# SCH_DC.net
KiCad netlist of a schematic drawn in EasyEDA
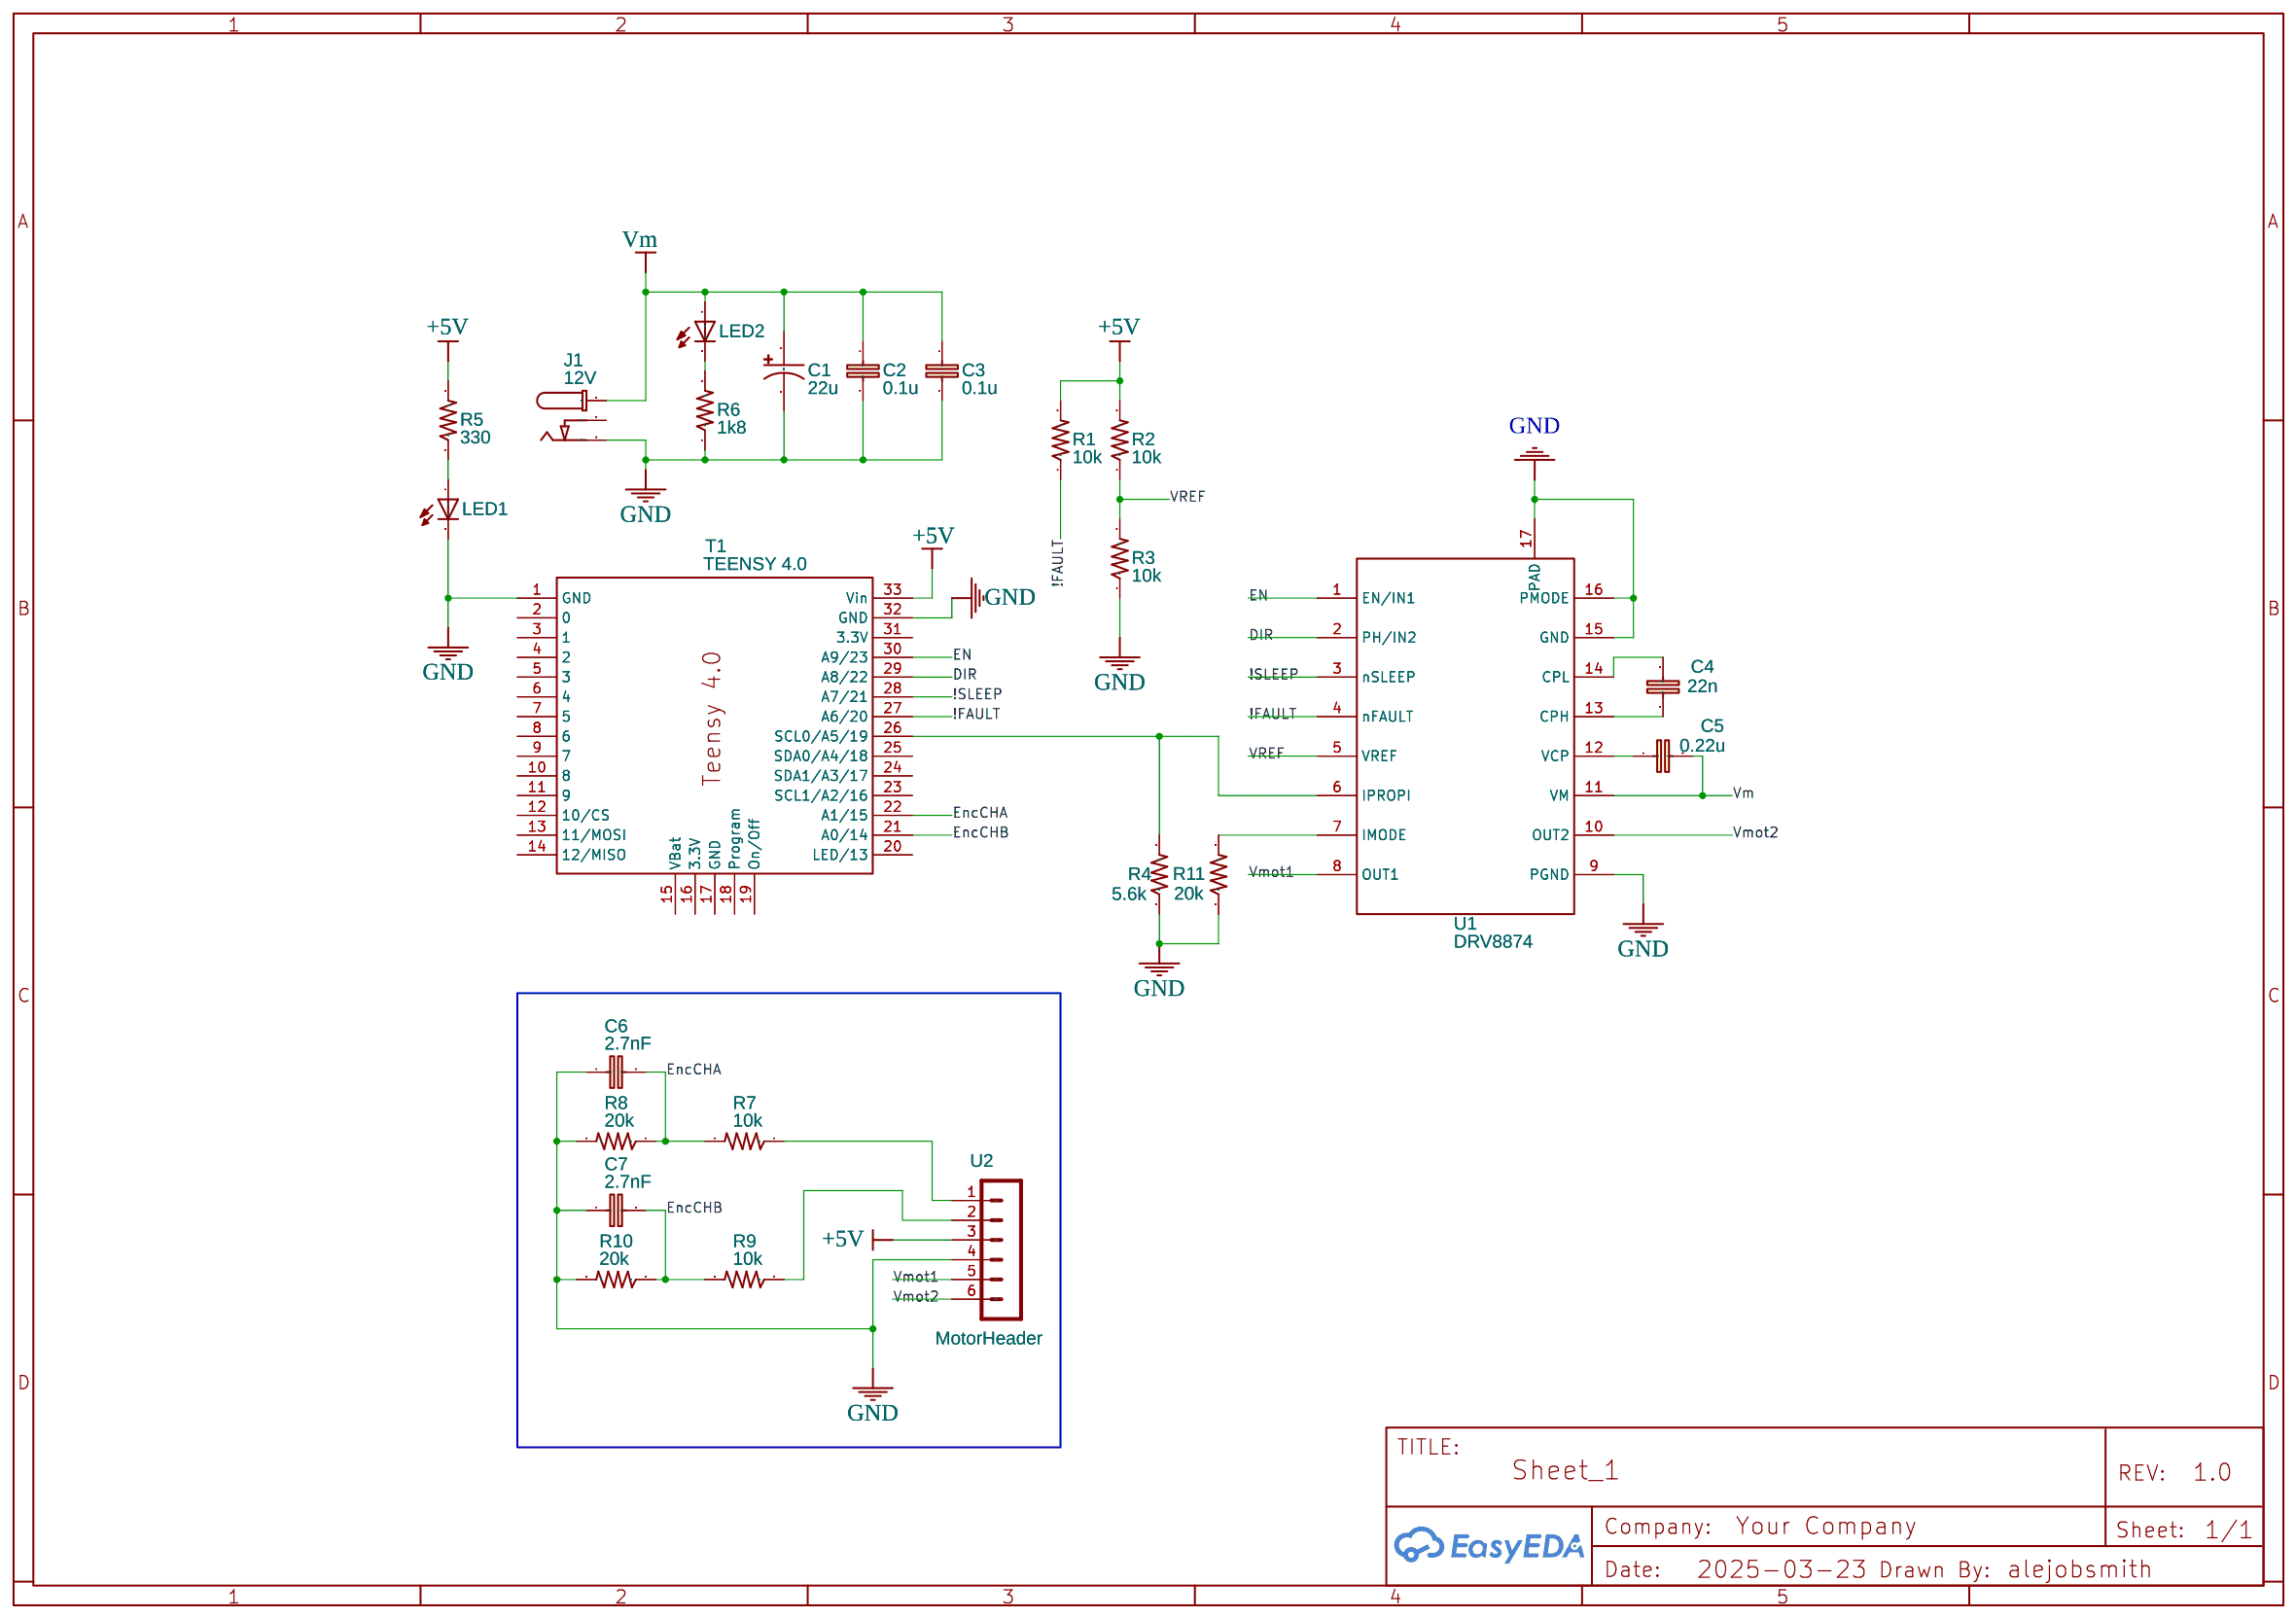
[diagram p0: schematic sheet]

(export (version "E")
  (design (tool "Eeschema 10.0.6"))
  (components
    (comp (ref "C1") (value "22u") (libsource (lib "") (part "Cap_Electrolytic(SMD)_D5.0XH5.5_US")))
    (comp (ref "C2") (value "0.1u") (libsource (lib "") (part "CAPACITOR_NPOL-1206_1")))
    (comp (ref "C3") (value "0.1u") (libsource (lib "") (part "CAPACITOR_NPOL-1206_1")))
    (comp (ref "C4") (value "22n") (libsource (lib "") (part "CAPACITOR_NPOL-1206_2")))
    (comp (ref "C5") (value "0.22u") (libsource (lib "") (part "CAPACITOR_NPOL-1206")))
    (comp (ref "C6") (value "2.7nF") (libsource (lib "") (part "CAPACITOR_NPOL-1206")))
    (comp (ref "C7") (value "2.7nF") (libsource (lib "") (part "CAPACITOR_NPOL-1206")))
    (comp (ref "J1") (value "12V") (libsource (lib "") (part "CON_DC_M-DC_PTH2")))
    (comp (ref "LED1") (value "LED_5MM") (libsource (lib "") (part "LED_5MM")))
    (comp (ref "LED2") (value "LED_5MM") (libsource (lib "") (part "LED_5MM")))
    (comp (ref "R1") (value "10k") (libsource (lib "") (part "R-US_R1206_1")))
    (comp (ref "R2") (value "10k") (libsource (lib "") (part "R-US_R1206_1")))
    (comp (ref "R3") (value "10k") (libsource (lib "") (part "R-US_R1206_1")))
    (comp (ref "R4") (value "5.6k") (libsource (lib "") (part "R-US_R1206_1")))
    (comp (ref "R5") (value "330") (libsource (lib "") (part "R-US_R1206_1")))
    (comp (ref "R6") (value "1k8") (libsource (lib "") (part "R-US_R1206_1")))
    (comp (ref "R7") (value "10k") (libsource (lib "") (part "R-US_R1206")))
    (comp (ref "R8") (value "20k") (libsource (lib "") (part "R-US_R1206")))
    (comp (ref "R9") (value "10k") (libsource (lib "") (part "R-US_R1206")))
    (comp (ref "R10") (value "20k") (libsource (lib "") (part "R-US_R1206")))
    (comp (ref "R11") (value "20k") (libsource (lib "") (part "R-US_R1206_1")))
    (comp (ref "T1")
      (value "TEENSY 4.0")
      (fields (field (name "Manufacturer") "PJRC"))
      (libsource (lib "") (part "TEENSY 4.0"))
    )
    (comp (ref "U1")
      (value "DRV8874")
      (fields (field (name "Manufacturer") "Texas Instruments"))
      (libsource (lib "") (part "DRV8874"))
    )
    (comp (ref "U2") (value "MotorHeader") (libsource (lib "") (part "HEADER-06X1-MALE")))
  )
  (nets
    (net (code "1") (name "+5V") (class "Default")
      (node (ref "R1") (pin "2") (pinfunction "2_2") (pintype "unspecified"))
      (node (ref "R2") (pin "2") (pinfunction "2_2") (pintype "unspecified"))
      (node (ref "R5") (pin "2") (pinfunction "2_2") (pintype "unspecified"))
      (node (ref "T1") (pin "33") (pinfunction "Vin_33") (pintype "unspecified"))
      (node (ref "U2") (pin "3") (pinfunction "3_3") (pintype "unspecified"))
    )
    (net (code "2") (name "/!FAULT") (class "Default")
      (node (ref "R1") (pin "1") (pinfunction "1_1") (pintype "unspecified"))
      (node (ref "T1") (pin "27") (pinfunction "A6/20_27") (pintype "unspecified"))
      (node (ref "U1") (pin "4") (pinfunction "nFAULT_4") (pintype "unspecified"))
    )
    (net (code "3") (name "/!SLEEP") (class "Default")
      (node (ref "T1") (pin "28") (pinfunction "A7/21_28") (pintype "unspecified"))
      (node (ref "U1") (pin "3") (pinfunction "nSLEEP_3") (pintype "unspecified"))
    )
    (net (code "4") (name "/DIR") (class "Default")
      (node (ref "T1") (pin "29") (pinfunction "A8/22_29") (pintype "unspecified"))
      (node (ref "U1") (pin "2") (pinfunction "PH/IN2_2") (pintype "unspecified"))
    )
    (net (code "5") (name "/EN") (class "Default")
      (node (ref "T1") (pin "30") (pinfunction "A9/23_30") (pintype "unspecified"))
      (node (ref "U1") (pin "1") (pinfunction "EN/IN1_1") (pintype "unspecified"))
    )
    (net (code "6") (name "/EncCHA") (class "Default")
      (node (ref "C6") (pin "2") (pinfunction "2_2") (pintype "unspecified"))
      (node (ref "R7") (pin "2") (pinfunction "2_2") (pintype "unspecified"))
      (node (ref "R8") (pin "1") (pinfunction "1_1") (pintype "unspecified"))
      (node (ref "T1") (pin "22") (pinfunction "A1/15_22") (pintype "unspecified"))
    )
    (net (code "7") (name "/EncCHB") (class "Default")
      (node (ref "C7") (pin "2") (pinfunction "2_2") (pintype "unspecified"))
      (node (ref "R10") (pin "1") (pinfunction "1_1") (pintype "unspecified"))
      (node (ref "R9") (pin "2") (pinfunction "2_2") (pintype "unspecified"))
      (node (ref "T1") (pin "21") (pinfunction "A0/14_21") (pintype "unspecified"))
    )
    (net (code "8") (name "/VREF") (class "Default")
      (node (ref "R2") (pin "1") (pinfunction "1_1") (pintype "unspecified"))
      (node (ref "R3") (pin "2") (pinfunction "2_2") (pintype "unspecified"))
      (node (ref "U1") (pin "5") (pinfunction "VREF_5") (pintype "unspecified"))
    )
    (net (code "9") (name "/Vmot1") (class "Default")
      (node (ref "U1") (pin "8") (pinfunction "OUT1_8") (pintype "unspecified"))
      (node (ref "U2") (pin "5") (pinfunction "5_5") (pintype "unspecified"))
    )
    (net (code "10") (name "/Vmot2") (class "Default")
      (node (ref "U1") (pin "10") (pinfunction "OUT2_10") (pintype "unspecified"))
      (node (ref "U2") (pin "6") (pinfunction "6_6") (pintype "unspecified"))
    )
    (net (code "11") (name "GND") (class "Default")
      (node (ref "C1") (pin "2") (pinfunction "2_2") (pintype "unspecified"))
      (node (ref "C2") (pin "2") (pinfunction "2_2") (pintype "unspecified"))
      (node (ref "C3") (pin "2") (pinfunction "2_2") (pintype "unspecified"))
      (node (ref "C6") (pin "1") (pinfunction "1_1") (pintype "unspecified"))
      (node (ref "C7") (pin "1") (pinfunction "1_1") (pintype "unspecified"))
      (node (ref "J1") (pin "P3") (pinfunction "P2_P3") (pintype "unspecified"))
      (node (ref "LED1") (pin "2") (pinfunction "C_2") (pintype "unspecified"))
      (node (ref "R10") (pin "2") (pinfunction "2_2") (pintype "unspecified"))
      (node (ref "R11") (pin "1") (pinfunction "1_1") (pintype "unspecified"))
      (node (ref "R3") (pin "1") (pinfunction "1_1") (pintype "unspecified"))
      (node (ref "R4") (pin "1") (pinfunction "1_1") (pintype "unspecified"))
      (node (ref "R6") (pin "1") (pinfunction "1_1") (pintype "unspecified"))
      (node (ref "R8") (pin "2") (pinfunction "2_2") (pintype "unspecified"))
      (node (ref "T1") (pin "1") (pinfunction "GND_1") (pintype "unspecified"))
      (node (ref "T1") (pin "32") (pinfunction "GND_32") (pintype "unspecified"))
      (node (ref "U1") (pin "15") (pinfunction "GND_15") (pintype "unspecified"))
      (node (ref "U1") (pin "16") (pinfunction "PMODE_16") (pintype "unspecified"))
      (node (ref "U1") (pin "17") (pinfunction "PAD_17") (pintype "unspecified"))
      (node (ref "U1") (pin "9") (pinfunction "PGND_9") (pintype "unspecified"))
      (node (ref "U2") (pin "4") (pinfunction "4_4") (pintype "unspecified"))
    )
    (net (code "12") (name "Net-(LED1-A)") (class "Default")
      (node (ref "LED1") (pin "1") (pinfunction "A_1") (pintype "unspecified"))
      (node (ref "R5") (pin "1") (pinfunction "1_1") (pintype "unspecified"))
    )
    (net (code "13") (name "Net-(LED2-C)") (class "Default")
      (node (ref "LED2") (pin "2") (pinfunction "C_2") (pintype "unspecified"))
      (node (ref "R6") (pin "2") (pinfunction "2_2") (pintype "unspecified"))
    )
    (net (code "14") (name "Net-(R7-Pad1)") (class "Default")
      (node (ref "R7") (pin "1") (pinfunction "1_1") (pintype "unspecified"))
      (node (ref "U2") (pin "1") (pinfunction "1_1") (pintype "unspecified"))
    )
    (net (code "15") (name "Net-(R9-Pad1)") (class "Default")
      (node (ref "R9") (pin "1") (pinfunction "1_1") (pintype "unspecified"))
      (node (ref "U2") (pin "2") (pinfunction "2_2") (pintype "unspecified"))
    )
    (net (code "16") (name "Net-(T1-SCL0{slash}A5{slash}19)") (class "Default")
      (node (ref "R4") (pin "2") (pinfunction "2_2") (pintype "unspecified"))
      (node (ref "T1") (pin "26") (pinfunction "SCL0/A5/19_26") (pintype "unspecified"))
      (node (ref "U1") (pin "6") (pinfunction "IPROPI_6") (pintype "unspecified"))
    )
    (net (code "17") (name "Net-(U1-CPH)") (class "Default")
      (node (ref "C4") (pin "1") (pinfunction "1_1") (pintype "unspecified"))
      (node (ref "U1") (pin "13") (pinfunction "CPH_13") (pintype "unspecified"))
    )
    (net (code "18") (name "Net-(U1-CPL)") (class "Default")
      (node (ref "C4") (pin "2") (pinfunction "2_2") (pintype "unspecified"))
      (node (ref "U1") (pin "14") (pinfunction "CPL_14") (pintype "unspecified"))
    )
    (net (code "19") (name "Net-(U1-IMODE)") (class "Default")
      (node (ref "R11") (pin "2") (pinfunction "2_2") (pintype "unspecified"))
      (node (ref "U1") (pin "7") (pinfunction "IMODE_7") (pintype "unspecified"))
    )
    (net (code "20") (name "Net-(U1-VCP)") (class "Default")
      (node (ref "C5") (pin "1") (pinfunction "1_1") (pintype "unspecified"))
      (node (ref "U1") (pin "12") (pinfunction "VCP_12") (pintype "unspecified"))
    )
    (net (code "21") (name "Vm") (class "Default")
      (node (ref "C1") (pin "1") (pinfunction "1_1") (pintype "unspecified"))
      (node (ref "C2") (pin "1") (pinfunction "1_1") (pintype "unspecified"))
      (node (ref "C3") (pin "1") (pinfunction "1_1") (pintype "unspecified"))
      (node (ref "C5") (pin "2") (pinfunction "2_2") (pintype "unspecified"))
      (node (ref "J1") (pin "P1") (pinfunction "P1_P1") (pintype "unspecified"))
      (node (ref "LED2") (pin "1") (pinfunction "A_1") (pintype "unspecified"))
      (node (ref "U1") (pin "11") (pinfunction "VM_11") (pintype "unspecified"))
    )
    (net (code "22") (name "unconnected-(J1-P3-PadP2)") (class "Default")
      (node (ref "J1") (pin "P2") (pinfunction "P3_P2") (pintype "unspecified"))
    )
    (net (code "23") (name "unconnected-(T1-0-Pad2)") (class "Default")
      (node (ref "T1") (pin "2") (pinfunction "0_2") (pintype "unspecified"))
    )
    (net (code "24") (name "unconnected-(T1-1-Pad3)") (class "Default")
      (node (ref "T1") (pin "3") (pinfunction "1_3") (pintype "unspecified"))
    )
    (net (code "25") (name "unconnected-(T1-2-Pad4)") (class "Default")
      (node (ref "T1") (pin "4") (pinfunction "2_4") (pintype "unspecified"))
    )
    (net (code "26") (name "unconnected-(T1-3-Pad5)") (class "Default")
      (node (ref "T1") (pin "5") (pinfunction "3_5") (pintype "unspecified"))
    )
    (net (code "27") (name "unconnected-(T1-3.3V-Pad16)") (class "Default")
      (node (ref "T1") (pin "16") (pinfunction "3.3V_16") (pintype "unspecified"))
    )
    (net (code "28") (name "unconnected-(T1-3.3V-Pad31)") (class "Default")
      (node (ref "T1") (pin "31") (pinfunction "3.3V_31") (pintype "unspecified"))
    )
    (net (code "29") (name "unconnected-(T1-4-Pad6)") (class "Default")
      (node (ref "T1") (pin "6") (pinfunction "4_6") (pintype "unspecified"))
    )
    (net (code "30") (name "unconnected-(T1-5-Pad7)") (class "Default")
      (node (ref "T1") (pin "7") (pinfunction "5_7") (pintype "unspecified"))
    )
    (net (code "31") (name "unconnected-(T1-6-Pad8)") (class "Default")
      (node (ref "T1") (pin "8") (pinfunction "6_8") (pintype "unspecified"))
    )
    (net (code "32") (name "unconnected-(T1-7-Pad9)") (class "Default")
      (node (ref "T1") (pin "9") (pinfunction "7_9") (pintype "unspecified"))
    )
    (net (code "33") (name "unconnected-(T1-8-Pad10)") (class "Default")
      (node (ref "T1") (pin "10") (pinfunction "8_10") (pintype "unspecified"))
    )
    (net (code "34") (name "unconnected-(T1-9-Pad11)") (class "Default")
      (node (ref "T1") (pin "11") (pinfunction "9_11") (pintype "unspecified"))
    )
    (net (code "35") (name "unconnected-(T1-10{slash}CS-Pad12)") (class "Default")
      (node (ref "T1") (pin "12") (pinfunction "10/CS_12") (pintype "unspecified"))
    )
    (net (code "36") (name "unconnected-(T1-11{slash}MOSI-Pad13)") (class "Default")
      (node (ref "T1") (pin "13") (pinfunction "11/MOSI_13") (pintype "unspecified"))
    )
    (net (code "37") (name "unconnected-(T1-12{slash}MISO-Pad14)") (class "Default")
      (node (ref "T1") (pin "14") (pinfunction "12/MISO_14") (pintype "unspecified"))
    )
    (net (code "38") (name "unconnected-(T1-GND-Pad17)") (class "Default")
      (node (ref "T1") (pin "17") (pinfunction "GND_17") (pintype "unspecified"))
    )
    (net (code "39") (name "unconnected-(T1-LED{slash}13-Pad20)") (class "Default")
      (node (ref "T1") (pin "20") (pinfunction "LED/13_20") (pintype "unspecified"))
    )
    (net (code "40") (name "unconnected-(T1-On{slash}Off-Pad19)") (class "Default")
      (node (ref "T1") (pin "19") (pinfunction "On/Off_19") (pintype "unspecified"))
    )
    (net (code "41") (name "unconnected-(T1-Program-Pad18)") (class "Default")
      (node (ref "T1") (pin "18") (pinfunction "Program_18") (pintype "unspecified"))
    )
    (net (code "42") (name "unconnected-(T1-SCL1{slash}A2{slash}16-Pad23)") (class "Default")
      (node (ref "T1") (pin "23") (pinfunction "SCL1/A2/16_23") (pintype "unspecified"))
    )
    (net (code "43") (name "unconnected-(T1-SDA0{slash}A4{slash}18-Pad25)") (class "Default")
      (node (ref "T1") (pin "25") (pinfunction "SDA0/A4/18_25") (pintype "unspecified"))
    )
    (net (code "44") (name "unconnected-(T1-SDA1{slash}A3{slash}17-Pad24)") (class "Default")
      (node (ref "T1") (pin "24") (pinfunction "SDA1/A3/17_24") (pintype "unspecified"))
    )
    (net (code "45") (name "unconnected-(T1-VBat-Pad15)") (class "Default")
      (node (ref "T1") (pin "15") (pinfunction "VBat_15") (pintype "unspecified"))
    )
  )
)
